# Extension_connectors.net
KiCad netlist of a schematic drawn in Altium Designer
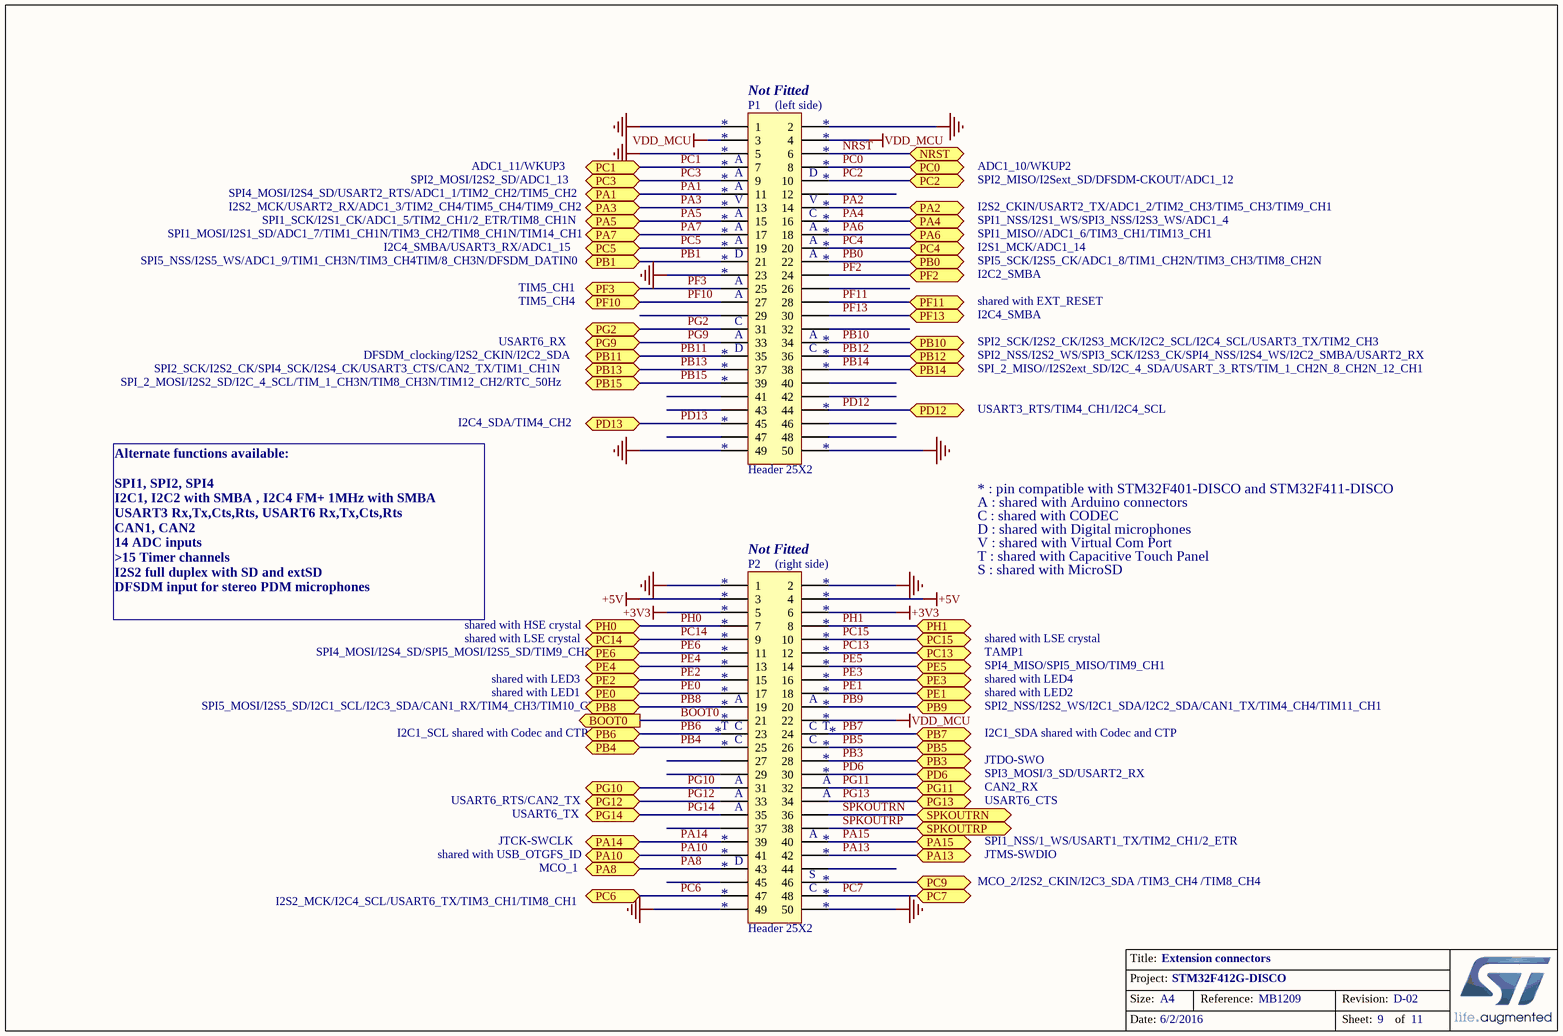
[diagram p0: Extension_connectors.SchDoc]

(export (version "E")
  (design (tool "Eeschema 10.0.6"))
  (components
    (comp (ref "P1")
      (value "Header 25X2")
      (footprint "HDR_2X25_2R54_W")
      (description "Header, 25-Pin, Dual row")
      (fields (field (name "PUBLISHER") "Altium Limited"))
      (libsource (lib "Miscellaneous Connectors") (part "Header 25X2"))
    )
    (comp (ref "P2")
      (value "Header 25X2")
      (footprint "HDR_2X25_2R54_W")
      (description "Header, 25-Pin, Dual row")
      (fields (field (name "PUBLISHER") "Altium Limited"))
      (libsource (lib "Miscellaneous Connectors") (part "Header 25X2"))
    )
  )
  (nets
    (net (code "1") (name "+3V3") (class "Default")
      (node (ref "P2") (pin "5") (pinfunction "5_5") (pintype "passive"))
      (node (ref "P2") (pin "6") (pinfunction "6_6") (pintype "passive"))
    )
    (net (code "2") (name "+5V") (class "Default")
      (node (ref "P2") (pin "3") (pinfunction "3_3") (pintype "passive"))
      (node (ref "P2") (pin "4") (pinfunction "4_4") (pintype "passive"))
    )
    (net (code "3") (name "/BOOT0") (class "Default")
      (node (ref "P2") (pin "21") (pinfunction "21_21") (pintype "passive"))
    )
    (net (code "4") (name "/NRST") (class "Default")
      (node (ref "P1") (pin "6") (pinfunction "6_6") (pintype "passive"))
    )
    (net (code "5") (name "/PA1") (class "Default")
      (node (ref "P1") (pin "11") (pinfunction "11_11") (pintype "passive"))
    )
    (net (code "6") (name "/PA2") (class "Default")
      (node (ref "P1") (pin "14") (pinfunction "14_14") (pintype "passive"))
    )
    (net (code "7") (name "/PA3") (class "Default")
      (node (ref "P1") (pin "13") (pinfunction "13_13") (pintype "passive"))
    )
    (net (code "8") (name "/PA4") (class "Default")
      (node (ref "P1") (pin "16") (pinfunction "16_16") (pintype "passive"))
    )
    (net (code "9") (name "/PA5") (class "Default")
      (node (ref "P1") (pin "15") (pinfunction "15_15") (pintype "passive"))
    )
    (net (code "10") (name "/PA6") (class "Default")
      (node (ref "P1") (pin "18") (pinfunction "18_18") (pintype "passive"))
    )
    (net (code "11") (name "/PA7") (class "Default")
      (node (ref "P1") (pin "17") (pinfunction "17_17") (pintype "passive"))
    )
    (net (code "12") (name "/PA8") (class "Default")
      (node (ref "P2") (pin "43") (pinfunction "43_43") (pintype "passive"))
    )
    (net (code "13") (name "/PA10") (class "Default")
      (node (ref "P2") (pin "41") (pinfunction "41_41") (pintype "passive"))
    )
    (net (code "14") (name "/PA13") (class "Default")
      (node (ref "P2") (pin "42") (pinfunction "42_42") (pintype "passive"))
    )
    (net (code "15") (name "/PA14") (class "Default")
      (node (ref "P2") (pin "39") (pinfunction "39_39") (pintype "passive"))
    )
    (net (code "16") (name "/PA15") (class "Default")
      (node (ref "P2") (pin "40") (pinfunction "40_40") (pintype "passive"))
    )
    (net (code "17") (name "/PB0") (class "Default")
      (node (ref "P1") (pin "22") (pinfunction "22_22") (pintype "passive"))
    )
    (net (code "18") (name "/PB1") (class "Default")
      (node (ref "P1") (pin "21") (pinfunction "21_21") (pintype "passive"))
    )
    (net (code "19") (name "/PB3") (class "Default")
      (node (ref "P2") (pin "28") (pinfunction "28_28") (pintype "passive"))
    )
    (net (code "20") (name "/PB4") (class "Default")
      (node (ref "P2") (pin "25") (pinfunction "25_25") (pintype "passive"))
    )
    (net (code "21") (name "/PB5") (class "Default")
      (node (ref "P2") (pin "26") (pinfunction "26_26") (pintype "passive"))
    )
    (net (code "22") (name "/PB6") (class "Default")
      (node (ref "P2") (pin "23") (pinfunction "23_23") (pintype "passive"))
    )
    (net (code "23") (name "/PB7") (class "Default")
      (node (ref "P2") (pin "24") (pinfunction "24_24") (pintype "passive"))
    )
    (net (code "24") (name "/PB8") (class "Default")
      (node (ref "P2") (pin "19") (pinfunction "19_19") (pintype "passive"))
    )
    (net (code "25") (name "/PB9") (class "Default")
      (node (ref "P2") (pin "20") (pinfunction "20_20") (pintype "passive"))
    )
    (net (code "26") (name "/PB10") (class "Default")
      (node (ref "P1") (pin "34") (pinfunction "34_34") (pintype "passive"))
    )
    (net (code "27") (name "/PB11") (class "Default")
      (node (ref "P1") (pin "35") (pinfunction "35_35") (pintype "passive"))
    )
    (net (code "28") (name "/PB12") (class "Default")
      (node (ref "P1") (pin "36") (pinfunction "36_36") (pintype "passive"))
    )
    (net (code "29") (name "/PB13") (class "Default")
      (node (ref "P1") (pin "37") (pinfunction "37_37") (pintype "passive"))
    )
    (net (code "30") (name "/PB14") (class "Default")
      (node (ref "P1") (pin "38") (pinfunction "38_38") (pintype "passive"))
    )
    (net (code "31") (name "/PB15") (class "Default")
      (node (ref "P1") (pin "39") (pinfunction "39_39") (pintype "passive"))
    )
    (net (code "32") (name "/PC0") (class "Default")
      (node (ref "P1") (pin "8") (pinfunction "8_8") (pintype "passive"))
    )
    (net (code "33") (name "/PC1") (class "Default")
      (node (ref "P1") (pin "7") (pinfunction "7_7") (pintype "passive"))
    )
    (net (code "34") (name "/PC2") (class "Default")
      (node (ref "P1") (pin "10") (pinfunction "10_10") (pintype "passive"))
    )
    (net (code "35") (name "/PC3") (class "Default")
      (node (ref "P1") (pin "9") (pinfunction "9_9") (pintype "passive"))
    )
    (net (code "36") (name "/PC4") (class "Default")
      (node (ref "P1") (pin "20") (pinfunction "20_20") (pintype "passive"))
    )
    (net (code "37") (name "/PC5") (class "Default")
      (node (ref "P1") (pin "19") (pinfunction "19_19") (pintype "passive"))
    )
    (net (code "38") (name "/PC6") (class "Default")
      (node (ref "P2") (pin "47") (pinfunction "47_47") (pintype "passive"))
    )
    (net (code "39") (name "/PC7") (class "Default")
      (node (ref "P2") (pin "48") (pinfunction "48_48") (pintype "passive"))
    )
    (net (code "40") (name "/PC9") (class "Default")
      (node (ref "P2") (pin "46") (pinfunction "46_46") (pintype "passive"))
    )
    (net (code "41") (name "/PC13") (class "Default")
      (node (ref "P2") (pin "12") (pinfunction "12_12") (pintype "passive"))
    )
    (net (code "42") (name "/PC14") (class "Default")
      (node (ref "P2") (pin "9") (pinfunction "9_9") (pintype "passive"))
    )
    (net (code "43") (name "/PC15") (class "Default")
      (node (ref "P2") (pin "10") (pinfunction "10_10") (pintype "passive"))
    )
    (net (code "44") (name "/PD6") (class "Default")
      (node (ref "P2") (pin "30") (pinfunction "30_30") (pintype "passive"))
    )
    (net (code "45") (name "/PD12") (class "Default")
      (node (ref "P1") (pin "44") (pinfunction "44_44") (pintype "passive"))
    )
    (net (code "46") (name "/PD13") (class "Default")
      (node (ref "P1") (pin "45") (pinfunction "45_45") (pintype "passive"))
    )
    (net (code "47") (name "/PE0") (class "Default")
      (node (ref "P2") (pin "17") (pinfunction "17_17") (pintype "passive"))
    )
    (net (code "48") (name "/PE1") (class "Default")
      (node (ref "P2") (pin "18") (pinfunction "18_18") (pintype "passive"))
    )
    (net (code "49") (name "/PE2") (class "Default")
      (node (ref "P2") (pin "15") (pinfunction "15_15") (pintype "passive"))
    )
    (net (code "50") (name "/PE3") (class "Default")
      (node (ref "P2") (pin "16") (pinfunction "16_16") (pintype "passive"))
    )
    (net (code "51") (name "/PE4") (class "Default")
      (node (ref "P2") (pin "13") (pinfunction "13_13") (pintype "passive"))
    )
    (net (code "52") (name "/PE5") (class "Default")
      (node (ref "P2") (pin "14") (pinfunction "14_14") (pintype "passive"))
    )
    (net (code "53") (name "/PE6") (class "Default")
      (node (ref "P2") (pin "11") (pinfunction "11_11") (pintype "passive"))
    )
    (net (code "54") (name "/PF2") (class "Default")
      (node (ref "P1") (pin "24") (pinfunction "24_24") (pintype "passive"))
    )
    (net (code "55") (name "/PF3") (class "Default")
      (node (ref "P1") (pin "25") (pinfunction "25_25") (pintype "passive"))
    )
    (net (code "56") (name "/PF10") (class "Default")
      (node (ref "P1") (pin "27") (pinfunction "27_27") (pintype "passive"))
    )
    (net (code "57") (name "/PF11") (class "Default")
      (node (ref "P1") (pin "28") (pinfunction "28_28") (pintype "passive"))
    )
    (net (code "58") (name "/PF13") (class "Default")
      (node (ref "P1") (pin "30") (pinfunction "30_30") (pintype "passive"))
    )
    (net (code "59") (name "/PG2") (class "Default")
      (node (ref "P1") (pin "31") (pinfunction "31_31") (pintype "passive"))
    )
    (net (code "60") (name "/PG9") (class "Default")
      (node (ref "P1") (pin "33") (pinfunction "33_33") (pintype "passive"))
    )
    (net (code "61") (name "/PG10") (class "Default")
      (node (ref "P2") (pin "31") (pinfunction "31_31") (pintype "passive"))
    )
    (net (code "62") (name "/PG11") (class "Default")
      (node (ref "P2") (pin "32") (pinfunction "32_32") (pintype "passive"))
    )
    (net (code "63") (name "/PG12") (class "Default")
      (node (ref "P2") (pin "33") (pinfunction "33_33") (pintype "passive"))
    )
    (net (code "64") (name "/PG13") (class "Default")
      (node (ref "P2") (pin "34") (pinfunction "34_34") (pintype "passive"))
    )
    (net (code "65") (name "/PG14") (class "Default")
      (node (ref "P2") (pin "35") (pinfunction "35_35") (pintype "passive"))
    )
    (net (code "66") (name "/PH0") (class "Default")
      (node (ref "P2") (pin "7") (pinfunction "7_7") (pintype "passive"))
    )
    (net (code "67") (name "/PH1") (class "Default")
      (node (ref "P2") (pin "8") (pinfunction "8_8") (pintype "passive"))
    )
    (net (code "68") (name "/SPKOUTRN") (class "Default")
      (node (ref "P2") (pin "36") (pinfunction "36_36") (pintype "passive"))
    )
    (net (code "69") (name "/SPKOUTRP") (class "Default")
      (node (ref "P2") (pin "38") (pinfunction "38_38") (pintype "passive"))
    )
    (net (code "70") (name "GND") (class "Default")
      (node (ref "P1") (pin "1") (pinfunction "1_1") (pintype "passive"))
      (node (ref "P1") (pin "2") (pinfunction "2_2") (pintype "passive"))
      (node (ref "P1") (pin "23") (pinfunction "23_23") (pintype "passive"))
      (node (ref "P1") (pin "49") (pinfunction "49_49") (pintype "passive"))
      (node (ref "P1") (pin "5") (pinfunction "5_5") (pintype "passive"))
      (node (ref "P1") (pin "50") (pinfunction "50_50") (pintype "passive"))
      (node (ref "P2") (pin "1") (pinfunction "1_1") (pintype "passive"))
      (node (ref "P2") (pin "2") (pinfunction "2_2") (pintype "passive"))
      (node (ref "P2") (pin "49") (pinfunction "49_49") (pintype "passive"))
      (node (ref "P2") (pin "50") (pinfunction "50_50") (pintype "passive"))
    )
    (net (code "71") (name "VDD_MCU") (class "Default")
      (node (ref "P1") (pin "3") (pinfunction "3_3") (pintype "passive"))
      (node (ref "P1") (pin "4") (pinfunction "4_4") (pintype "passive"))
      (node (ref "P2") (pin "22") (pinfunction "22_22") (pintype "passive"))
    )
    (net (code "72") (name "unconnected-(P1-Pad12)") (class "Default")
      (node (ref "P1") (pin "12") (pinfunction "12_12") (pintype "passive"))
    )
    (net (code "73") (name "unconnected-(P1-Pad26)") (class "Default")
      (node (ref "P1") (pin "26") (pinfunction "26_26") (pintype "passive"))
    )
    (net (code "74") (name "unconnected-(P1-Pad29)") (class "Default")
      (node (ref "P1") (pin "29") (pinfunction "29_29") (pintype "passive"))
    )
    (net (code "75") (name "unconnected-(P1-Pad32)") (class "Default")
      (node (ref "P1") (pin "32") (pinfunction "32_32") (pintype "passive"))
    )
    (net (code "76") (name "unconnected-(P1-Pad40)") (class "Default")
      (node (ref "P1") (pin "40") (pinfunction "40_40") (pintype "passive"))
    )
    (net (code "77") (name "unconnected-(P1-Pad41)") (class "Default")
      (node (ref "P1") (pin "41") (pinfunction "41_41") (pintype "passive"))
    )
    (net (code "78") (name "unconnected-(P1-Pad42)") (class "Default")
      (node (ref "P1") (pin "42") (pinfunction "42_42") (pintype "passive"))
    )
    (net (code "79") (name "unconnected-(P1-Pad43)") (class "Default")
      (node (ref "P1") (pin "43") (pinfunction "43_43") (pintype "passive"))
    )
    (net (code "80") (name "unconnected-(P1-Pad46)") (class "Default")
      (node (ref "P1") (pin "46") (pinfunction "46_46") (pintype "passive"))
    )
    (net (code "81") (name "unconnected-(P1-Pad47)") (class "Default")
      (node (ref "P1") (pin "47") (pinfunction "47_47") (pintype "passive"))
    )
    (net (code "82") (name "unconnected-(P1-Pad48)") (class "Default")
      (node (ref "P1") (pin "48") (pinfunction "48_48") (pintype "passive"))
    )
    (net (code "83") (name "unconnected-(P2-Pad27)") (class "Default")
      (node (ref "P2") (pin "27") (pinfunction "27_27") (pintype "passive"))
    )
    (net (code "84") (name "unconnected-(P2-Pad29)") (class "Default")
      (node (ref "P2") (pin "29") (pinfunction "29_29") (pintype "passive"))
    )
    (net (code "85") (name "unconnected-(P2-Pad37)") (class "Default")
      (node (ref "P2") (pin "37") (pinfunction "37_37") (pintype "passive"))
    )
    (net (code "86") (name "unconnected-(P2-Pad44)") (class "Default")
      (node (ref "P2") (pin "44") (pinfunction "44_44") (pintype "passive"))
    )
    (net (code "87") (name "unconnected-(P2-Pad45)") (class "Default")
      (node (ref "P2") (pin "45") (pinfunction "45_45") (pintype "passive"))
    )
  )
)
